# FPSController.net
KiCad netlist of a schematic drawn in Altium Designer
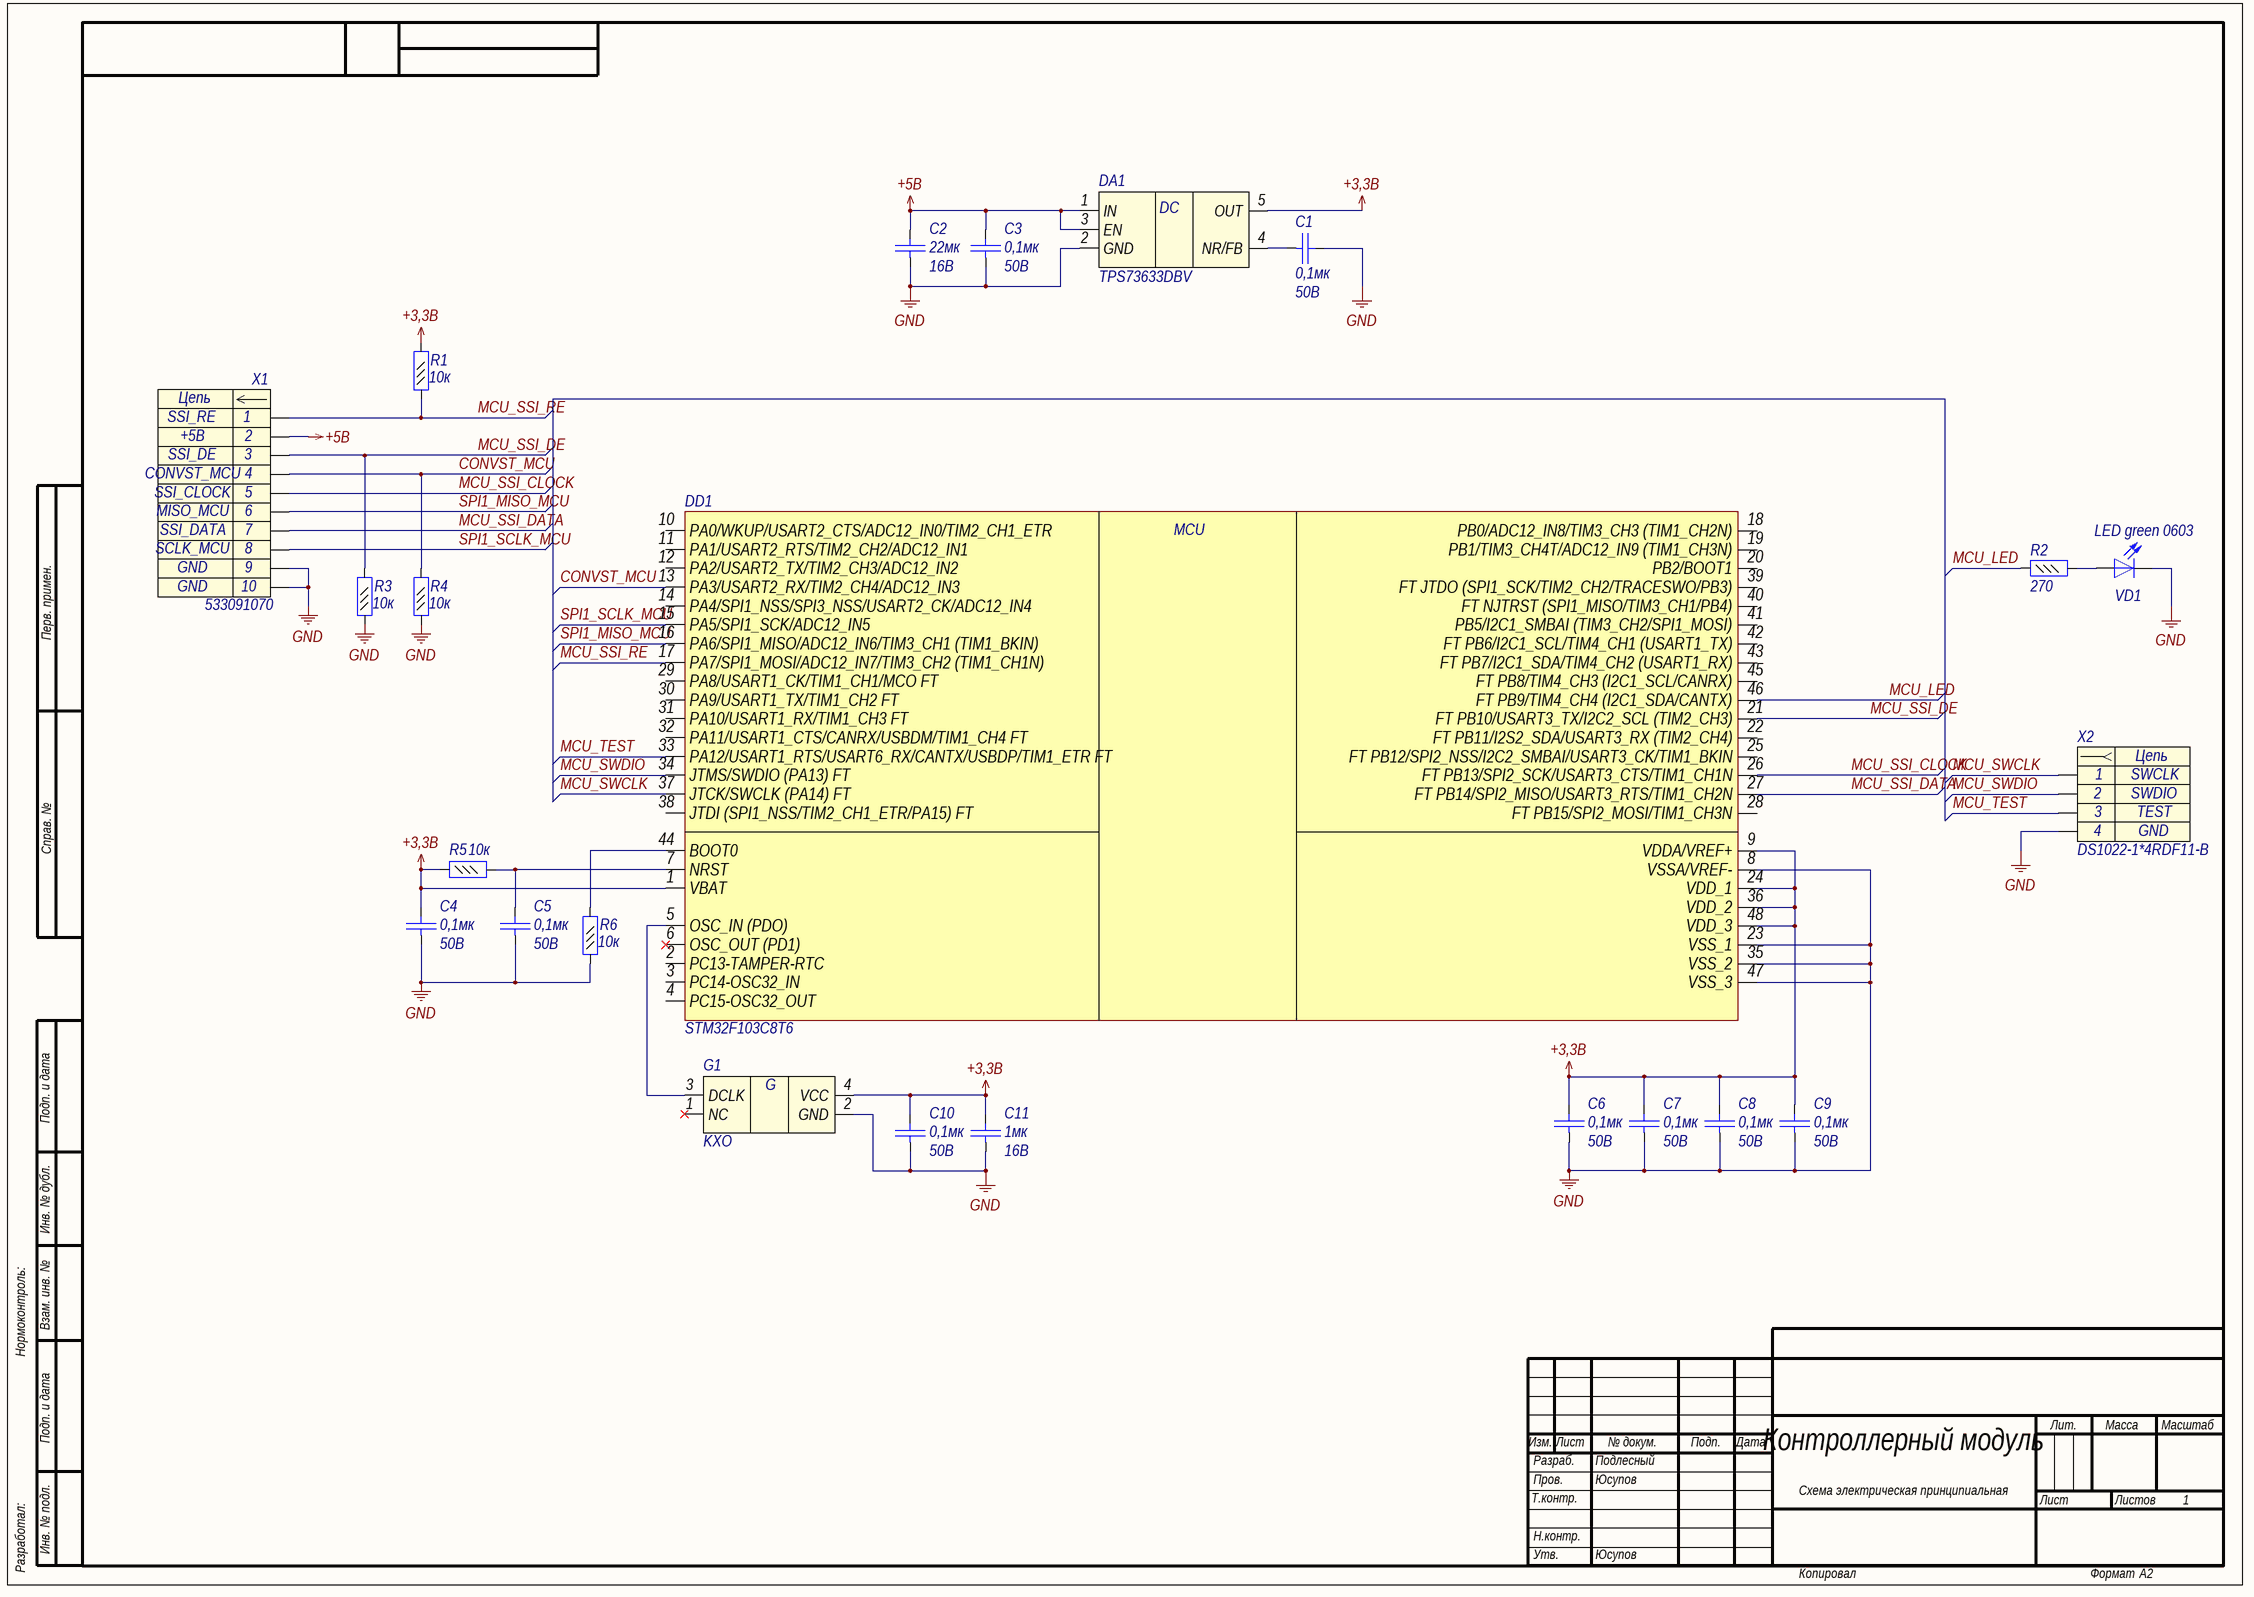
[diagram p0: FPSController.SchDoc]

(export (version "E")
  (design (tool "Eeschema 10.0.6"))
  (components
    (comp (ref "C1")
      (value "0,1мк")
      (footprint "C0402")
      (description "Конденсатор")
      (fields (field (name "VOLTAGE") "50В") (field (name "PART NUMBER") "GRM155R71H104KE14D"))
      (libsource (lib "MOP44") (part "Capacitor"))
    )
    (comp (ref "C2")
      (value "22мк")
      (footprint "C1210")
      (description "Конденсатор")
      (fields (field (name "VOLTAGE") "16B") (field (name "PART NUMBER") "C3225X7R1C226M"))
      (libsource (lib "MOP44") (part "Capacitor"))
    )
    (comp (ref "C3")
      (value "0,1мк")
      (footprint "C0402")
      (description "Конденсатор")
      (fields (field (name "VOLTAGE") "50В") (field (name "PART NUMBER") "GRM155R71H104KE14D"))
      (libsource (lib "MOP44") (part "Capacitor"))
    )
    (comp (ref "C4")
      (value "0,1мк")
      (footprint "C0402")
      (description "Конденсатор")
      (fields (field (name "VOLTAGE") "50В") (field (name "PART NUMBER") "GRM155R71H104KE14D"))
      (libsource (lib "MOP44") (part "Capacitor"))
    )
    (comp (ref "C5")
      (value "0,1мк")
      (footprint "C0402")
      (description "Конденсатор")
      (fields (field (name "VOLTAGE") "50В") (field (name "PART NUMBER") "GRM155R71H104KE14D"))
      (libsource (lib "MOP44") (part "Capacitor"))
    )
    (comp (ref "C6")
      (value "0,1мк")
      (footprint "C0402")
      (description "Конденсатор")
      (fields (field (name "VOLTAGE") "50В") (field (name "PART NUMBER") "GRM155R71H104KE14D"))
      (libsource (lib "MOP44") (part "Capacitor"))
    )
    (comp (ref "C7")
      (value "0,1мк")
      (footprint "C0402")
      (description "Конденсатор")
      (fields (field (name "VOLTAGE") "50В") (field (name "PART NUMBER") "GRM155R71H104KE14D"))
      (libsource (lib "MOP44") (part "Capacitor"))
    )
    (comp (ref "C8")
      (value "0,1мк")
      (footprint "C0402")
      (description "Конденсатор")
      (fields (field (name "VOLTAGE") "50В") (field (name "PART NUMBER") "GRM155R71H104KE14D"))
      (libsource (lib "MOP44") (part "Capacitor"))
    )
    (comp (ref "C9")
      (value "0,1мк")
      (footprint "C0402")
      (description "Конденсатор")
      (fields (field (name "VOLTAGE") "50В") (field (name "PART NUMBER") "GRM155R71H104KE14D"))
      (libsource (lib "MOP44") (part "Capacitor"))
    )
    (comp (ref "C10")
      (value "0,1мк")
      (footprint "C0402")
      (description "Конденсатор")
      (fields
        (field (name "VOLTAGE") "50В")
        (field (name "PART NUMBER") "GRM155R71H104KE14D")
        (field (name "Comment") "Capacitor")
      )
      (libsource (lib "MOP44") (part "Capacitor"))
    )
    (comp (ref "C11")
      (value "1мк")
      (footprint "C0603")
      (description "Конденсатор")
      (fields
        (field (name "VOLTAGE") "16B")
        (field (name "PART NUMBER") "GRM188R71C105KA12D**")
        (field (name "Comment") "Capacitor")
      )
      (libsource (lib "MOP44") (part "Capacitor"))
    )
    (comp (ref "DA1")
      (value "TPS736DBV")
      (footprint "SOT23-5")
      (description "400-mA Low-Dropout Regulator with Reverse Current  Protection")
      (fields (field (name "PART NUMBER") "TPS73633DBV") (field (name "MANUFACTURER") "Texas Instruments"))
      (libsource (lib "MOP44") (part "TPS736DBV"))
    )
    (comp (ref "DD1")
      (value "STM32F103C8T6")
      (footprint "LQFP48")
      (libsource (lib "MOP44") (part "STM32F103C8T6"))
    )
    (comp (ref "G1")
      (value "KXO")
      (footprint "QSMD7x5.2x1.8")
      (description "Кварц. генер. 32.768 МГц (HCMOS/TTL)")
      (fields (field (name "PART NUMBER") "KXO-V97"))
      (libsource (lib "MOP44") (part "KXO"))
    )
    (comp (ref "R1")
      (value "10к")
      (footprint "R0402")
      (description "Резистор")
      (fields (field (name "PART NUMBER") "RC0402FR-0710KL") (field (name "POWER") "0,062Вт"))
      (libsource (lib "") (part "Resistor_0,062Вт_1"))
    )
    (comp (ref "R2")
      (value "270")
      (footprint "R0402")
      (description "Резистор")
      (fields (field (name "PART NUMBER") "RC0402FR-07270RL") (field (name "POWER") "0,062Вт"))
      (libsource (lib "MOP44") (part "Resistor_0,062Вт"))
    )
    (comp (ref "R3")
      (value "10к")
      (footprint "R0402")
      (description "Резистор")
      (fields (field (name "PART NUMBER") "RC0402FR-0710KL") (field (name "POWER") "0,062Вт"))
      (libsource (lib "") (part "Resistor_0,062Вт_1"))
    )
    (comp (ref "R4")
      (value "10к")
      (footprint "R0402")
      (description "Резистор")
      (fields (field (name "PART NUMBER") "RC0402FR-0710KL") (field (name "POWER") "0,062Вт"))
      (libsource (lib "") (part "Resistor_0,062Вт_1"))
    )
    (comp (ref "R5")
      (value "10к")
      (footprint "R0402")
      (description "Резистор")
      (fields (field (name "PART NUMBER") "RC0402FR-0710KL") (field (name "POWER") "0,062Вт"))
      (libsource (lib "MOP44") (part "Resistor_0,062Вт"))
    )
    (comp (ref "R6")
      (value "10к")
      (footprint "R0402")
      (description "Резистор")
      (fields (field (name "PART NUMBER") "RC0402FR-0710KL") (field (name "POWER") "0,062Вт"))
      (libsource (lib "") (part "Resistor_0,062Вт_1"))
    )
    (comp (ref "VD1")
      (value "LED")
      (footprint "L_0603_GREEN")
      (description "Светодиод")
      (fields (field (name "PART NAME") "LED green 0603") (field (name "PART NUMBER") "TO-1608BC-PG"))
      (libsource (lib "MOP44") (part "LED"))
    )
    (comp (ref "X1")
      (value "Header_10_plg")
      (footprint "SlimStack-10pin-angl-plg")
      (description "Разъем - 10 конт. вилка")
      (fields (field (name "PART NUMBER") "533091070"))
      (libsource (lib "MOP44") (part "Header_10_plg"))
    )
    (comp (ref "X2")
      (value "Header_4_sct")
      (footprint "PLS-4R")
      (description "Разъем - 4 конт. розетка")
      (fields (field (name "PART NUMBER") "DS1022-1*4RDF11-B"))
      (libsource (lib "MOP44") (part "Header_4_sct"))
    )
  )
  (nets
    (net (code "1") (name "+3,3B") (class "Default")
      (node (ref "C10") (pin "2") (pinfunction "2_2") (pintype "passive"))
      (node (ref "C11") (pin "2") (pinfunction "2_2") (pintype "passive"))
      (node (ref "C4") (pin "2") (pinfunction "2_2") (pintype "passive"))
      (node (ref "C6") (pin "2") (pinfunction "2_2") (pintype "passive"))
      (node (ref "C7") (pin "2") (pinfunction "2_2") (pintype "passive"))
      (node (ref "C8") (pin "2") (pinfunction "2_2") (pintype "passive"))
      (node (ref "C9") (pin "2") (pinfunction "2_2") (pintype "passive"))
      (node (ref "DA1") (pin "5") (pinfunction "OUT_5") (pintype "power_in"))
      (node (ref "DD1") (pin "1") (pinfunction "VBAT_1") (pintype "passive"))
      (node (ref "DD1") (pin "24") (pinfunction "VDD_1_24") (pintype "passive"))
      (node (ref "DD1") (pin "36") (pinfunction "VDD_2_36") (pintype "passive"))
      (node (ref "DD1") (pin "48") (pinfunction "VDD_3_48") (pintype "passive"))
      (node (ref "DD1") (pin "9") (pinfunction "VDDA/VREF+_9") (pintype "passive"))
      (node (ref "G1") (pin "4") (pinfunction "VCC_4") (pintype "power_in"))
      (node (ref "R1") (pin "2") (pinfunction "2_2") (pintype "passive"))
      (node (ref "R5") (pin "1") (pinfunction "1_1") (pintype "passive"))
    )
    (net (code "2") (name "+5B") (class "Default")
      (node (ref "C2") (pin "2") (pinfunction "2_2") (pintype "passive"))
      (node (ref "C3") (pin "2") (pinfunction "2_2") (pintype "passive"))
      (node (ref "DA1") (pin "1") (pinfunction "IN_1") (pintype "power_in"))
      (node (ref "DA1") (pin "3") (pinfunction "EN_3") (pintype "power_in"))
      (node (ref "X1") (pin "2") (pinfunction "2_2") (pintype "passive"))
    )
    (net (code "3") (name "/CONVST_MCU") (class "Default")
      (node (ref "DD1") (pin "13") (pinfunction "PA3/USART2_RX/TIM2_CH4/ADC12_IN3_13") (pintype "passive"))
      (node (ref "R4") (pin "2") (pinfunction "2_2") (pintype "passive"))
      (node (ref "X1") (pin "4") (pinfunction "4_4") (pintype "passive"))
    )
    (net (code "4") (name "/MCU_LED") (class "Default")
      (node (ref "DD1") (pin "46") (pinfunction "FT_PB9/TIM4_CH4_(I2C1_SDA/CANTX)_46") (pintype "passive"))
      (node (ref "R2") (pin "1") (pinfunction "1_1") (pintype "passive"))
    )
    (net (code "5") (name "/MCU_SSI_CLOCK") (class "Default")
      (node (ref "DD1") (pin "26") (pinfunction "FT_PB13/SPI2_SCK/USART3_CTS/TIM1_CH1N_26") (pintype "passive"))
      (node (ref "X1") (pin "5") (pinfunction "5_5") (pintype "passive"))
    )
    (net (code "6") (name "/MCU_SSI_DATA") (class "Default")
      (node (ref "DD1") (pin "27") (pinfunction "FT_PB14/SPI2_MISO/USART3_RTS/TIM1_CH2N_27") (pintype "passive"))
      (node (ref "X1") (pin "7") (pinfunction "7_7") (pintype "passive"))
    )
    (net (code "7") (name "/MCU_SSI_DE") (class "Default")
      (node (ref "DD1") (pin "21") (pinfunction "FT_PB10/USART3_TX/I2C2_SCL_(TIM2_CH3)_21") (pintype "passive"))
      (node (ref "R3") (pin "2") (pinfunction "2_2") (pintype "passive"))
      (node (ref "X1") (pin "3") (pinfunction "3_3") (pintype "passive"))
    )
    (net (code "8") (name "/MCU_SSI_RE") (class "Default")
      (node (ref "DD1") (pin "17") (pinfunction "PA7/SPI1_MOSI/ADC12_IN7/TIM3_CH2_(TIM1_CH1N)_17") (pintype "passive"))
      (node (ref "R1") (pin "1") (pinfunction "1_1") (pintype "passive"))
      (node (ref "X1") (pin "1") (pinfunction "1_1") (pintype "passive"))
    )
    (net (code "9") (name "/MCU_SWCLK") (class "Default")
      (node (ref "DD1") (pin "37") (pinfunction "JTCK/SWCLK_(PA14)_FT_37") (pintype "passive"))
      (node (ref "X2") (pin "1") (pinfunction "1_1") (pintype "passive"))
    )
    (net (code "10") (name "/MCU_SWDIO") (class "Default")
      (node (ref "DD1") (pin "34") (pinfunction "JTMS/SWDIO_(PA13)_FT_34") (pintype "passive"))
      (node (ref "X2") (pin "2") (pinfunction "2_2") (pintype "passive"))
    )
    (net (code "11") (name "/MCU_TEST") (class "Default")
      (node (ref "DD1") (pin "33") (pinfunction "PA12/USART1_RTS/USART6_RX/CANTX/USBDP/TIM1_ETR_FT_33") (pintype "passive"))
      (node (ref "X2") (pin "3") (pinfunction "3_3") (pintype "passive"))
    )
    (net (code "12") (name "/SPI1_MISO_MCU") (class "Default")
      (node (ref "DD1") (pin "16") (pinfunction "PA6/SPI1_MISO/ADC12_IN6/TIM3_CH1_(TIM1_BKIN)_16") (pintype "passive"))
      (node (ref "X1") (pin "6") (pinfunction "6_6") (pintype "passive"))
    )
    (net (code "13") (name "/SPI1_SCLK_MCU") (class "Default")
      (node (ref "DD1") (pin "15") (pinfunction "PA5/SPI1_SCK/ADC12_IN5_15") (pintype "passive"))
      (node (ref "X1") (pin "8") (pinfunction "8_8") (pintype "passive"))
    )
    (net (code "14") (name "GND") (class "Default")
      (node (ref "C1") (pin "2") (pinfunction "2_2") (pintype "passive"))
      (node (ref "C10") (pin "1") (pinfunction "1_1") (pintype "passive"))
      (node (ref "C11") (pin "1") (pinfunction "1_1") (pintype "passive"))
      (node (ref "C2") (pin "1") (pinfunction "1_1") (pintype "passive"))
      (node (ref "C3") (pin "1") (pinfunction "1_1") (pintype "passive"))
      (node (ref "C4") (pin "1") (pinfunction "1_1") (pintype "passive"))
      (node (ref "C5") (pin "1") (pinfunction "1_1") (pintype "passive"))
      (node (ref "C6") (pin "1") (pinfunction "1_1") (pintype "passive"))
      (node (ref "C7") (pin "1") (pinfunction "1_1") (pintype "passive"))
      (node (ref "C8") (pin "1") (pinfunction "1_1") (pintype "passive"))
      (node (ref "C9") (pin "1") (pinfunction "1_1") (pintype "passive"))
      (node (ref "DA1") (pin "2") (pinfunction "GND_2") (pintype "power_in"))
      (node (ref "DD1") (pin "23") (pinfunction "VSS_1_23") (pintype "passive"))
      (node (ref "DD1") (pin "35") (pinfunction "VSS_2_35") (pintype "passive"))
      (node (ref "DD1") (pin "47") (pinfunction "VSS_3_47") (pintype "passive"))
      (node (ref "DD1") (pin "8") (pinfunction "VSSA/VREF-_8") (pintype "passive"))
      (node (ref "G1") (pin "2") (pinfunction "GND_2") (pintype "power_in"))
      (node (ref "R3") (pin "1") (pinfunction "1_1") (pintype "passive"))
      (node (ref "R4") (pin "1") (pinfunction "1_1") (pintype "passive"))
      (node (ref "R6") (pin "1") (pinfunction "1_1") (pintype "passive"))
      (node (ref "VD1") (pin "1") (pinfunction "K_1") (pintype "passive"))
      (node (ref "X1") (pin "10") (pinfunction "10_10") (pintype "passive"))
      (node (ref "X1") (pin "9") (pinfunction "9_9") (pintype "passive"))
      (node (ref "X2") (pin "4") (pinfunction "4_4") (pintype "passive"))
    )
    (net (code "15") (name "Net-(DA1-NR{slash}FB)") (class "Default")
      (node (ref "C1") (pin "1") (pinfunction "1_1") (pintype "passive"))
      (node (ref "DA1") (pin "4") (pinfunction "NR/FB_4") (pintype "power_in"))
    )
    (net (code "16") (name "Net-(DD1-BOOT0)") (class "Default")
      (node (ref "DD1") (pin "44") (pinfunction "BOOT0_44") (pintype "passive"))
      (node (ref "R6") (pin "2") (pinfunction "2_2") (pintype "passive"))
    )
    (net (code "17") (name "Net-(DD1-NRST)") (class "Default")
      (node (ref "C5") (pin "2") (pinfunction "2_2") (pintype "passive"))
      (node (ref "DD1") (pin "7") (pinfunction "NRST_7") (pintype "passive"))
      (node (ref "R5") (pin "2") (pinfunction "2_2") (pintype "passive"))
    )
    (net (code "18") (name "Net-(DD1-OSC_IN_(PDO))") (class "Default")
      (node (ref "DD1") (pin "5") (pinfunction "OSC_IN_(PDO)_5") (pintype "passive"))
      (node (ref "G1") (pin "3") (pinfunction "DCLK_3") (pintype "power_in"))
    )
    (net (code "19") (name "Net-(VD1-A)") (class "Default")
      (node (ref "R2") (pin "2") (pinfunction "2_2") (pintype "passive"))
      (node (ref "VD1") (pin "2") (pinfunction "A_2") (pintype "passive"))
    )
    (net (code "20") (name "unconnected-(DD1-FT_JTDO_(SPI1_SCK{slash}TIM2_CH2{slash}TRACESWO{slash}PB3)-Pad39)") (class "Default")
      (node (ref "DD1") (pin "39") (pinfunction "FT_JTDO_(SPI1_SCK/TIM2_CH2/TRACESWO/PB3)_39") (pintype "passive"))
    )
    (net (code "21") (name "unconnected-(DD1-FT_NJTRST_(SPI1_MISO{slash}TIM3_CH1{slash}PB4)-Pad40)") (class "Default")
      (node (ref "DD1") (pin "40") (pinfunction "FT_NJTRST_(SPI1_MISO/TIM3_CH1/PB4)_40") (pintype "passive"))
    )
    (net (code "22") (name "unconnected-(DD1-FT_PB6{slash}I2C1_SCL{slash}TIM4_CH1_(USART1_TX)-Pad42)") (class "Default")
      (node (ref "DD1") (pin "42") (pinfunction "FT_PB6/I2C1_SCL/TIM4_CH1_(USART1_TX)_42") (pintype "passive"))
    )
    (net (code "23") (name "unconnected-(DD1-FT_PB7{slash}I2C1_SDA{slash}TIM4_CH2_(USART1_RX)-Pad43)") (class "Default")
      (node (ref "DD1") (pin "43") (pinfunction "FT_PB7/I2C1_SDA/TIM4_CH2_(USART1_RX)_43") (pintype "passive"))
    )
    (net (code "24") (name "unconnected-(DD1-FT_PB8{slash}TIM4_CH3_(I2C1_SCL{slash}CANRX)-Pad45)") (class "Default")
      (node (ref "DD1") (pin "45") (pinfunction "FT_PB8/TIM4_CH3_(I2C1_SCL/CANRX)_45") (pintype "passive"))
    )
    (net (code "25") (name "unconnected-(DD1-FT_PB11{slash}I2S2_SDA{slash}USART3_RX_(TIM2_CH4)-Pad22)") (class "Default")
      (node (ref "DD1") (pin "22") (pinfunction "FT_PB11/I2S2_SDA/USART3_RX_(TIM2_CH4)_22") (pintype "passive"))
    )
    (net (code "26") (name "unconnected-(DD1-FT_PB12{slash}SPI2_NSS{slash}I2C2_SMBAI{slash}USART3_CK{slash}TIM1_BKIN-Pad25)") (class "Default")
      (node (ref "DD1") (pin "25") (pinfunction "FT_PB12/SPI2_NSS/I2C2_SMBAI/USART3_CK/TIM1_BKIN_25") (pintype "passive"))
    )
    (net (code "27") (name "unconnected-(DD1-FT_PB15{slash}SPI2_MOSI{slash}TIM1_CH3N-Pad28)") (class "Default")
      (node (ref "DD1") (pin "28") (pinfunction "FT_PB15/SPI2_MOSI/TIM1_CH3N_28") (pintype "passive"))
    )
    (net (code "28") (name "unconnected-(DD1-JTDI_(SPI1_NSS{slash}TIM2_CH1_ETR{slash}PA15)_FT-Pad38)") (class "Default")
      (node (ref "DD1") (pin "38") (pinfunction "JTDI_(SPI1_NSS/TIM2_CH1_ETR/PA15)_FT_38") (pintype "passive"))
    )
    (net (code "29") (name "unconnected-(DD1-OSC_OUT_(PD1)-Pad6)") (class "Default")
      (node (ref "DD1") (pin "6") (pinfunction "OSC_OUT_(PD1)_6") (pintype "passive+no_connect"))
    )
    (net (code "30") (name "unconnected-(DD1-PA0{slash}WKUP{slash}USART2_CTS{slash}ADC12_IN0{slash}TIM2_CH1_ETR-Pad10)") (class "Default")
      (node (ref "DD1") (pin "10") (pinfunction "PA0/WKUP/USART2_CTS/ADC12_IN0/TIM2_CH1_ETR_10") (pintype "passive"))
    )
    (net (code "31") (name "unconnected-(DD1-PA1{slash}USART2_RTS{slash}TIM2_CH2{slash}ADC12_IN1-Pad11)") (class "Default")
      (node (ref "DD1") (pin "11") (pinfunction "PA1/USART2_RTS/TIM2_CH2/ADC12_IN1_11") (pintype "passive"))
    )
    (net (code "32") (name "unconnected-(DD1-PA2{slash}USART2_TX{slash}TIM2_CH3{slash}ADC12_IN2-Pad12)") (class "Default")
      (node (ref "DD1") (pin "12") (pinfunction "PA2/USART2_TX/TIM2_CH3/ADC12_IN2_12") (pintype "passive"))
    )
    (net (code "33") (name "unconnected-(DD1-PA4{slash}SPI1_NSS{slash}SPI3_NSS{slash}USART2_CK{slash}ADC12_IN4-Pad14)") (class "Default")
      (node (ref "DD1") (pin "14") (pinfunction "PA4/SPI1_NSS/SPI3_NSS/USART2_CK/ADC12_IN4_14") (pintype "passive"))
    )
    (net (code "34") (name "unconnected-(DD1-PA8{slash}USART1_CK{slash}TIM1_CH1{slash}MCO_FT-Pad29)") (class "Default")
      (node (ref "DD1") (pin "29") (pinfunction "PA8/USART1_CK/TIM1_CH1/MCO_FT_29") (pintype "passive"))
    )
    (net (code "35") (name "unconnected-(DD1-PA9{slash}USART1_TX{slash}TIM1_CH2_FT-Pad30)") (class "Default")
      (node (ref "DD1") (pin "30") (pinfunction "PA9/USART1_TX/TIM1_CH2_FT_30") (pintype "passive"))
    )
    (net (code "36") (name "unconnected-(DD1-PA10{slash}USART1_RX{slash}TIM1_CH3_FT-Pad31)") (class "Default")
      (node (ref "DD1") (pin "31") (pinfunction "PA10/USART1_RX/TIM1_CH3_FT_31") (pintype "passive"))
    )
    (net (code "37") (name "unconnected-(DD1-PA11{slash}USART1_CTS{slash}CANRX{slash}USBDM{slash}TIM1_CH4_FT-Pad32)") (class "Default")
      (node (ref "DD1") (pin "32") (pinfunction "PA11/USART1_CTS/CANRX/USBDM/TIM1_CH4_FT_32") (pintype "passive"))
    )
    (net (code "38") (name "unconnected-(DD1-PB0{slash}ADC12_IN8{slash}TIM3_CH3_(TIM1_CH2N)-Pad18)") (class "Default")
      (node (ref "DD1") (pin "18") (pinfunction "PB0/ADC12_IN8/TIM3_CH3_(TIM1_CH2N)_18") (pintype "passive"))
    )
    (net (code "39") (name "unconnected-(DD1-PB1{slash}TIM3_CH4T{slash}ADC12_IN9_(TIM1_CH3N)-Pad19)") (class "Default")
      (node (ref "DD1") (pin "19") (pinfunction "PB1/TIM3_CH4T/ADC12_IN9_(TIM1_CH3N)_19") (pintype "passive"))
    )
    (net (code "40") (name "unconnected-(DD1-PB2{slash}BOOT1-Pad20)") (class "Default")
      (node (ref "DD1") (pin "20") (pinfunction "PB2/BOOT1_20") (pintype "passive"))
    )
    (net (code "41") (name "unconnected-(DD1-PB5{slash}I2C1_SMBAI_(TIM3_CH2{slash}SPI1_MOSI)-Pad41)") (class "Default")
      (node (ref "DD1") (pin "41") (pinfunction "PB5/I2C1_SMBAI_(TIM3_CH2/SPI1_MOSI)_41") (pintype "passive"))
    )
    (net (code "42") (name "unconnected-(DD1-PC13-TAMPER-RTC-Pad2)") (class "Default")
      (node (ref "DD1") (pin "2") (pinfunction "PC13-TAMPER-RTC_2") (pintype "passive"))
    )
    (net (code "43") (name "unconnected-(DD1-PC14-OSC32_IN-Pad3)") (class "Default")
      (node (ref "DD1") (pin "3") (pinfunction "PC14-OSC32_IN_3") (pintype "passive"))
    )
    (net (code "44") (name "unconnected-(DD1-PC15-OSC32_OUT-Pad4)") (class "Default")
      (node (ref "DD1") (pin "4") (pinfunction "PC15-OSC32_OUT_4") (pintype "passive"))
    )
    (net (code "45") (name "unconnected-(G1-NC-Pad1)") (class "Default")
      (node (ref "G1") (pin "1") (pinfunction "NC_1") (pintype "power_in+no_connect"))
    )
  )
)
